# led_heart.net
KiCad netlist of a schematic drawn in EAGLE
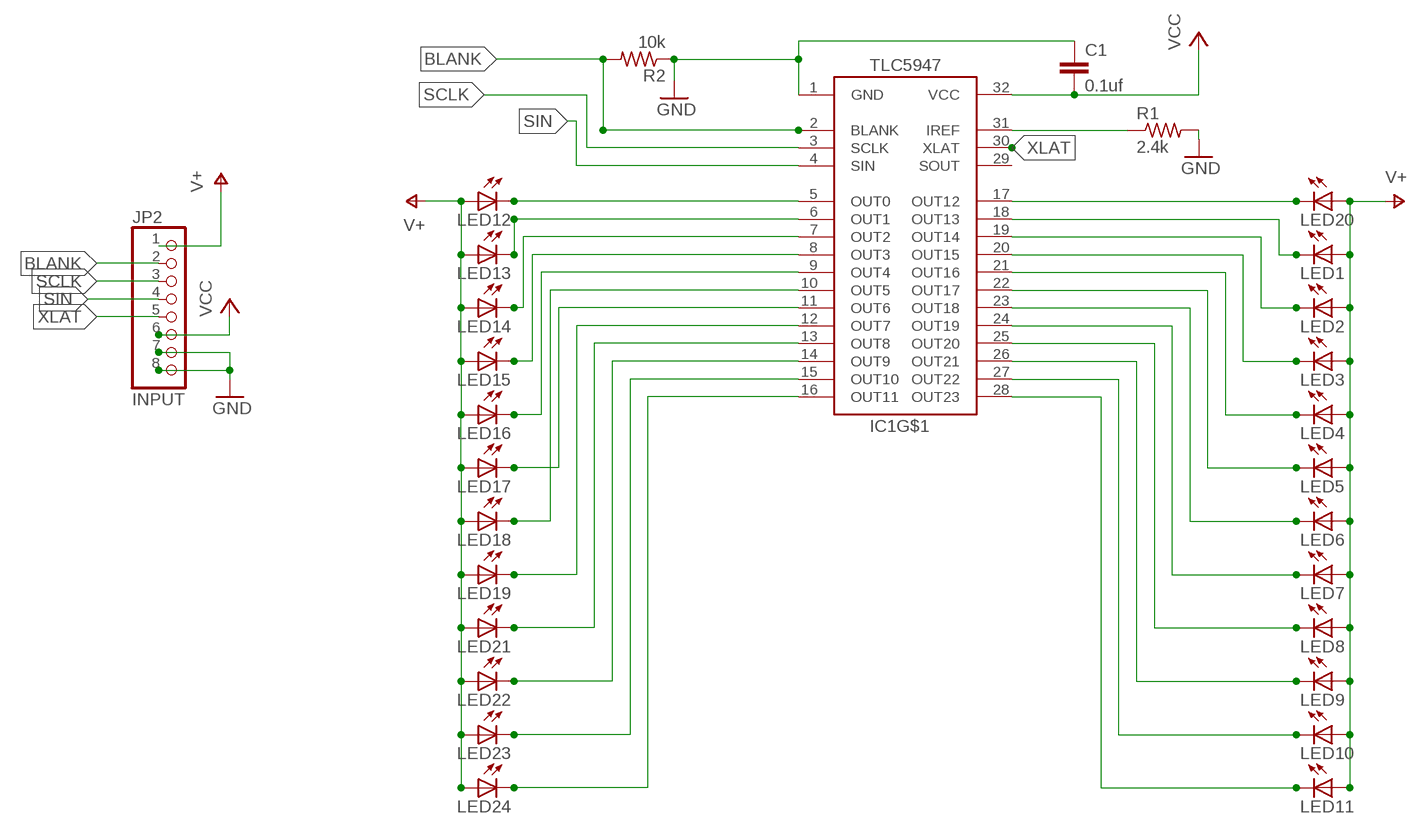
[diagram p0: schematic, sheet 1]

(export (version "E")
  (design (tool "Eeschema 10.0.6"))
  (components
    (comp (ref "C1")
      (value "0.1uf")
      (footprint "eagle-import:C0805")
      (libsource (lib "eagle-import") (part "C-EUC0805"))
    )
    (comp (ref "IC1")
      (value "TLC5947-DAP")
      (footprint "eagle-import:HTSSOP32DAP")
      (libsource (lib "eagle-import") (part "TLC5947-DAP"))
    )
    (comp (ref "JP2")
      (value "INPUT")
      (footprint "eagle-import:1X08-CLEANBIG")
      (libsource (lib "eagle-import") (part "PINHD-1X8CLEANBIG"))
    )
    (comp (ref "LED1")
      (value "LEDCHIPLED_1206")
      (footprint "eagle-import:CHIPLED_1206")
      (libsource (lib "eagle-import") (part "LEDCHIPLED_1206"))
    )
    (comp (ref "LED2")
      (value "LEDCHIPLED_1206")
      (footprint "eagle-import:CHIPLED_1206")
      (libsource (lib "eagle-import") (part "LEDCHIPLED_1206"))
    )
    (comp (ref "LED3")
      (value "LEDCHIPLED_1206")
      (footprint "eagle-import:CHIPLED_1206")
      (libsource (lib "eagle-import") (part "LEDCHIPLED_1206"))
    )
    (comp (ref "LED4")
      (value "LEDCHIPLED_1206")
      (footprint "eagle-import:CHIPLED_1206")
      (libsource (lib "eagle-import") (part "LEDCHIPLED_1206"))
    )
    (comp (ref "LED5")
      (value "LEDCHIPLED_1206")
      (footprint "eagle-import:CHIPLED_1206")
      (libsource (lib "eagle-import") (part "LEDCHIPLED_1206"))
    )
    (comp (ref "LED6")
      (value "LEDCHIPLED_1206")
      (footprint "eagle-import:CHIPLED_1206")
      (libsource (lib "eagle-import") (part "LEDCHIPLED_1206"))
    )
    (comp (ref "LED7")
      (value "LEDCHIPLED_1206")
      (footprint "eagle-import:CHIPLED_1206")
      (libsource (lib "eagle-import") (part "LEDCHIPLED_1206"))
    )
    (comp (ref "LED8")
      (value "LEDCHIPLED_1206")
      (footprint "eagle-import:CHIPLED_1206")
      (libsource (lib "eagle-import") (part "LEDCHIPLED_1206"))
    )
    (comp (ref "LED9")
      (value "LEDCHIPLED_1206")
      (footprint "eagle-import:CHIPLED_1206")
      (libsource (lib "eagle-import") (part "LEDCHIPLED_1206"))
    )
    (comp (ref "LED10")
      (value "LEDCHIPLED_1206")
      (footprint "eagle-import:CHIPLED_1206")
      (libsource (lib "eagle-import") (part "LEDCHIPLED_1206"))
    )
    (comp (ref "LED11")
      (value "LEDCHIPLED_1206")
      (footprint "eagle-import:CHIPLED_1206")
      (libsource (lib "eagle-import") (part "LEDCHIPLED_1206"))
    )
    (comp (ref "LED12")
      (value "LEDCHIPLED_1206")
      (footprint "eagle-import:CHIPLED_1206")
      (libsource (lib "eagle-import") (part "LEDCHIPLED_1206"))
    )
    (comp (ref "LED13")
      (value "LEDCHIPLED_1206")
      (footprint "eagle-import:CHIPLED_1206")
      (libsource (lib "eagle-import") (part "LEDCHIPLED_1206"))
    )
    (comp (ref "LED14")
      (value "LEDCHIPLED_1206")
      (footprint "eagle-import:CHIPLED_1206")
      (libsource (lib "eagle-import") (part "LEDCHIPLED_1206"))
    )
    (comp (ref "LED15")
      (value "LEDCHIPLED_1206")
      (footprint "eagle-import:CHIPLED_1206")
      (libsource (lib "eagle-import") (part "LEDCHIPLED_1206"))
    )
    (comp (ref "LED16")
      (value "LEDCHIPLED_1206")
      (footprint "eagle-import:CHIPLED_1206")
      (libsource (lib "eagle-import") (part "LEDCHIPLED_1206"))
    )
    (comp (ref "LED17")
      (value "LEDCHIPLED_1206")
      (footprint "eagle-import:CHIPLED_1206")
      (libsource (lib "eagle-import") (part "LEDCHIPLED_1206"))
    )
    (comp (ref "LED18")
      (value "LEDCHIPLED_1206")
      (footprint "eagle-import:CHIPLED_1206")
      (libsource (lib "eagle-import") (part "LEDCHIPLED_1206"))
    )
    (comp (ref "LED19")
      (value "LEDCHIPLED_1206")
      (footprint "eagle-import:CHIPLED_1206")
      (libsource (lib "eagle-import") (part "LEDCHIPLED_1206"))
    )
    (comp (ref "LED20")
      (value "LEDCHIPLED_1206")
      (footprint "eagle-import:CHIPLED_1206")
      (libsource (lib "eagle-import") (part "LEDCHIPLED_1206"))
    )
    (comp (ref "LED21")
      (value "LEDCHIPLED_1206")
      (footprint "eagle-import:CHIPLED_1206")
      (libsource (lib "eagle-import") (part "LEDCHIPLED_1206"))
    )
    (comp (ref "LED22")
      (value "LEDCHIPLED_1206")
      (footprint "eagle-import:CHIPLED_1206")
      (libsource (lib "eagle-import") (part "LEDCHIPLED_1206"))
    )
    (comp (ref "LED23")
      (value "LEDCHIPLED_1206")
      (footprint "eagle-import:CHIPLED_1206")
      (libsource (lib "eagle-import") (part "LEDCHIPLED_1206"))
    )
    (comp (ref "LED24")
      (value "LEDCHIPLED_1206")
      (footprint "eagle-import:CHIPLED_1206")
      (libsource (lib "eagle-import") (part "LEDCHIPLED_1206"))
    )
    (comp (ref "R1")
      (value "2.4k")
      (footprint "eagle-import:R0805")
      (libsource (lib "eagle-import") (part "R-US_R0805"))
    )
    (comp (ref "R2")
      (value "10k")
      (footprint "eagle-import:R0805")
      (libsource (lib "eagle-import") (part "R-US_R0805"))
    )
  )
  (nets
    (net (code "1") (name "BLANK") (class "Default")
      (node (ref "IC1") (pin "2") (pinfunction "BLANK_2") (pintype "input"))
      (node (ref "JP2") (pin "2") (pinfunction "2_2") (pintype "passive"))
      (node (ref "R2") (pin "2") (pinfunction "2_2") (pintype "passive"))
    )
    (net (code "2") (name "GND") (class "Default")
      (node (ref "C1") (pin "1") (pinfunction "1_1") (pintype "passive"))
      (node (ref "IC1") (pin "1") (pinfunction "GND_1") (pintype "power_in"))
      (node (ref "JP2") (pin "7") (pinfunction "7_7") (pintype "passive"))
      (node (ref "JP2") (pin "8") (pinfunction "8_8") (pintype "passive"))
      (node (ref "R1") (pin "2") (pinfunction "2_2") (pintype "passive"))
      (node (ref "R2") (pin "1") (pinfunction "1_1") (pintype "passive"))
    )
    (net (code "3") (name "Net-(IC1A-IREF)") (class "Default")
      (node (ref "IC1") (pin "31") (pinfunction "IREF_31") (pintype "bidirectional"))
      (node (ref "R1") (pin "1") (pinfunction "1_1") (pintype "passive"))
    )
    (net (code "4") (name "Net-(IC1A-OUT0)") (class "Default")
      (node (ref "IC1") (pin "5") (pinfunction "OUT0_5") (pintype "open_collector"))
      (node (ref "LED12") (pin "C") (pinfunction "C_C") (pintype "passive"))
    )
    (net (code "5") (name "Net-(IC1A-OUT1)") (class "Default")
      (node (ref "IC1") (pin "6") (pinfunction "OUT1_6") (pintype "open_collector"))
      (node (ref "LED13") (pin "C") (pinfunction "C_C") (pintype "passive"))
    )
    (net (code "6") (name "Net-(IC1A-OUT2)") (class "Default")
      (node (ref "IC1") (pin "7") (pinfunction "OUT2_7") (pintype "open_collector"))
      (node (ref "LED14") (pin "C") (pinfunction "C_C") (pintype "passive"))
    )
    (net (code "7") (name "Net-(IC1A-OUT3)") (class "Default")
      (node (ref "IC1") (pin "8") (pinfunction "OUT3_8") (pintype "open_collector"))
      (node (ref "LED15") (pin "C") (pinfunction "C_C") (pintype "passive"))
    )
    (net (code "8") (name "Net-(IC1A-OUT4)") (class "Default")
      (node (ref "IC1") (pin "9") (pinfunction "OUT4_9") (pintype "open_collector"))
      (node (ref "LED16") (pin "C") (pinfunction "C_C") (pintype "passive"))
    )
    (net (code "9") (name "Net-(IC1A-OUT5)") (class "Default")
      (node (ref "IC1") (pin "10") (pinfunction "OUT5_10") (pintype "open_collector"))
      (node (ref "LED18") (pin "C") (pinfunction "C_C") (pintype "passive"))
    )
    (net (code "10") (name "Net-(IC1A-OUT6)") (class "Default")
      (node (ref "IC1") (pin "11") (pinfunction "OUT6_11") (pintype "open_collector"))
      (node (ref "LED17") (pin "C") (pinfunction "C_C") (pintype "passive"))
    )
    (net (code "11") (name "Net-(IC1A-OUT7)") (class "Default")
      (node (ref "IC1") (pin "12") (pinfunction "OUT7_12") (pintype "open_collector"))
      (node (ref "LED19") (pin "C") (pinfunction "C_C") (pintype "passive"))
    )
    (net (code "12") (name "Net-(IC1A-OUT8)") (class "Default")
      (node (ref "IC1") (pin "13") (pinfunction "OUT8_13") (pintype "open_collector"))
      (node (ref "LED21") (pin "C") (pinfunction "C_C") (pintype "passive"))
    )
    (net (code "13") (name "Net-(IC1A-OUT9)") (class "Default")
      (node (ref "IC1") (pin "14") (pinfunction "OUT9_14") (pintype "open_collector"))
      (node (ref "LED22") (pin "C") (pinfunction "C_C") (pintype "passive"))
    )
    (net (code "14") (name "Net-(IC1A-OUT10)") (class "Default")
      (node (ref "IC1") (pin "15") (pinfunction "OUT10_15") (pintype "open_collector"))
      (node (ref "LED23") (pin "C") (pinfunction "C_C") (pintype "passive"))
    )
    (net (code "15") (name "Net-(IC1A-OUT11)") (class "Default")
      (node (ref "IC1") (pin "16") (pinfunction "OUT11_16") (pintype "open_collector"))
      (node (ref "LED24") (pin "C") (pinfunction "C_C") (pintype "passive"))
    )
    (net (code "16") (name "Net-(IC1A-OUT12)") (class "Default")
      (node (ref "IC1") (pin "17") (pinfunction "OUT12_17") (pintype "open_collector"))
      (node (ref "LED20") (pin "C") (pinfunction "C_C") (pintype "passive"))
    )
    (net (code "17") (name "Net-(IC1A-OUT13)") (class "Default")
      (node (ref "IC1") (pin "18") (pinfunction "OUT13_18") (pintype "open_collector"))
      (node (ref "LED1") (pin "C") (pinfunction "C_C") (pintype "passive"))
    )
    (net (code "18") (name "Net-(IC1A-OUT14)") (class "Default")
      (node (ref "IC1") (pin "19") (pinfunction "OUT14_19") (pintype "open_collector"))
      (node (ref "LED2") (pin "C") (pinfunction "C_C") (pintype "passive"))
    )
    (net (code "19") (name "Net-(IC1A-OUT15)") (class "Default")
      (node (ref "IC1") (pin "20") (pinfunction "OUT15_20") (pintype "open_collector"))
      (node (ref "LED3") (pin "C") (pinfunction "C_C") (pintype "passive"))
    )
    (net (code "20") (name "Net-(IC1A-OUT16)") (class "Default")
      (node (ref "IC1") (pin "21") (pinfunction "OUT16_21") (pintype "open_collector"))
      (node (ref "LED4") (pin "C") (pinfunction "C_C") (pintype "passive"))
    )
    (net (code "21") (name "Net-(IC1A-OUT17)") (class "Default")
      (node (ref "IC1") (pin "22") (pinfunction "OUT17_22") (pintype "open_collector"))
      (node (ref "LED5") (pin "C") (pinfunction "C_C") (pintype "passive"))
    )
    (net (code "22") (name "Net-(IC1A-OUT18)") (class "Default")
      (node (ref "IC1") (pin "23") (pinfunction "OUT18_23") (pintype "open_collector"))
      (node (ref "LED6") (pin "C") (pinfunction "C_C") (pintype "passive"))
    )
    (net (code "23") (name "Net-(IC1A-OUT19)") (class "Default")
      (node (ref "IC1") (pin "24") (pinfunction "OUT19_24") (pintype "open_collector"))
      (node (ref "LED7") (pin "C") (pinfunction "C_C") (pintype "passive"))
    )
    (net (code "24") (name "Net-(IC1A-OUT20)") (class "Default")
      (node (ref "IC1") (pin "25") (pinfunction "OUT20_25") (pintype "open_collector"))
      (node (ref "LED8") (pin "C") (pinfunction "C_C") (pintype "passive"))
    )
    (net (code "25") (name "Net-(IC1A-OUT21)") (class "Default")
      (node (ref "IC1") (pin "26") (pinfunction "OUT21_26") (pintype "open_collector"))
      (node (ref "LED9") (pin "C") (pinfunction "C_C") (pintype "passive"))
    )
    (net (code "26") (name "Net-(IC1A-OUT22)") (class "Default")
      (node (ref "IC1") (pin "27") (pinfunction "OUT22_27") (pintype "open_collector"))
      (node (ref "LED10") (pin "C") (pinfunction "C_C") (pintype "passive"))
    )
    (net (code "27") (name "Net-(IC1A-OUT23)") (class "Default")
      (node (ref "IC1") (pin "28") (pinfunction "OUT23_28") (pintype "open_collector"))
      (node (ref "LED11") (pin "C") (pinfunction "C_C") (pintype "passive"))
    )
    (net (code "28") (name "SCLK") (class "Default")
      (node (ref "IC1") (pin "3") (pinfunction "SCLK_3") (pintype "input"))
      (node (ref "JP2") (pin "3") (pinfunction "3_3") (pintype "passive"))
    )
    (net (code "29") (name "SIN") (class "Default")
      (node (ref "IC1") (pin "4") (pinfunction "SIN_4") (pintype "input"))
      (node (ref "JP2") (pin "4") (pinfunction "4_4") (pintype "passive"))
    )
    (net (code "30") (name "V+") (class "Default")
      (node (ref "JP2") (pin "1") (pinfunction "1_1") (pintype "passive"))
      (node (ref "LED1") (pin "A") (pinfunction "A_A") (pintype "passive"))
      (node (ref "LED10") (pin "A") (pinfunction "A_A") (pintype "passive"))
      (node (ref "LED11") (pin "A") (pinfunction "A_A") (pintype "passive"))
      (node (ref "LED12") (pin "A") (pinfunction "A_A") (pintype "passive"))
      (node (ref "LED13") (pin "A") (pinfunction "A_A") (pintype "passive"))
      (node (ref "LED14") (pin "A") (pinfunction "A_A") (pintype "passive"))
      (node (ref "LED15") (pin "A") (pinfunction "A_A") (pintype "passive"))
      (node (ref "LED16") (pin "A") (pinfunction "A_A") (pintype "passive"))
      (node (ref "LED17") (pin "A") (pinfunction "A_A") (pintype "passive"))
      (node (ref "LED18") (pin "A") (pinfunction "A_A") (pintype "passive"))
      (node (ref "LED19") (pin "A") (pinfunction "A_A") (pintype "passive"))
      (node (ref "LED2") (pin "A") (pinfunction "A_A") (pintype "passive"))
      (node (ref "LED20") (pin "A") (pinfunction "A_A") (pintype "passive"))
      (node (ref "LED21") (pin "A") (pinfunction "A_A") (pintype "passive"))
      (node (ref "LED22") (pin "A") (pinfunction "A_A") (pintype "passive"))
      (node (ref "LED23") (pin "A") (pinfunction "A_A") (pintype "passive"))
      (node (ref "LED24") (pin "A") (pinfunction "A_A") (pintype "passive"))
      (node (ref "LED3") (pin "A") (pinfunction "A_A") (pintype "passive"))
      (node (ref "LED4") (pin "A") (pinfunction "A_A") (pintype "passive"))
      (node (ref "LED5") (pin "A") (pinfunction "A_A") (pintype "passive"))
      (node (ref "LED6") (pin "A") (pinfunction "A_A") (pintype "passive"))
      (node (ref "LED7") (pin "A") (pinfunction "A_A") (pintype "passive"))
      (node (ref "LED8") (pin "A") (pinfunction "A_A") (pintype "passive"))
      (node (ref "LED9") (pin "A") (pinfunction "A_A") (pintype "passive"))
    )
    (net (code "31") (name "VCC") (class "Default")
      (node (ref "C1") (pin "2") (pinfunction "2_2") (pintype "passive"))
      (node (ref "IC1") (pin "32") (pinfunction "VCC_32") (pintype "power_in"))
      (node (ref "JP2") (pin "6") (pinfunction "6_6") (pintype "passive"))
    )
    (net (code "32") (name "XLAT") (class "Default")
      (node (ref "IC1") (pin "30") (pinfunction "XLAT_30") (pintype "input"))
      (node (ref "JP2") (pin "5") (pinfunction "5_5") (pintype "passive"))
    )
    (net (code "33") (name "unconnected-(IC1A-SOUT-Pad29)") (class "Default")
      (node (ref "IC1") (pin "29") (pinfunction "SOUT_29") (pintype "output"))
    )
  )
)
